# Battery_charger.net
KiCad netlist of a schematic drawn in Altium Designer
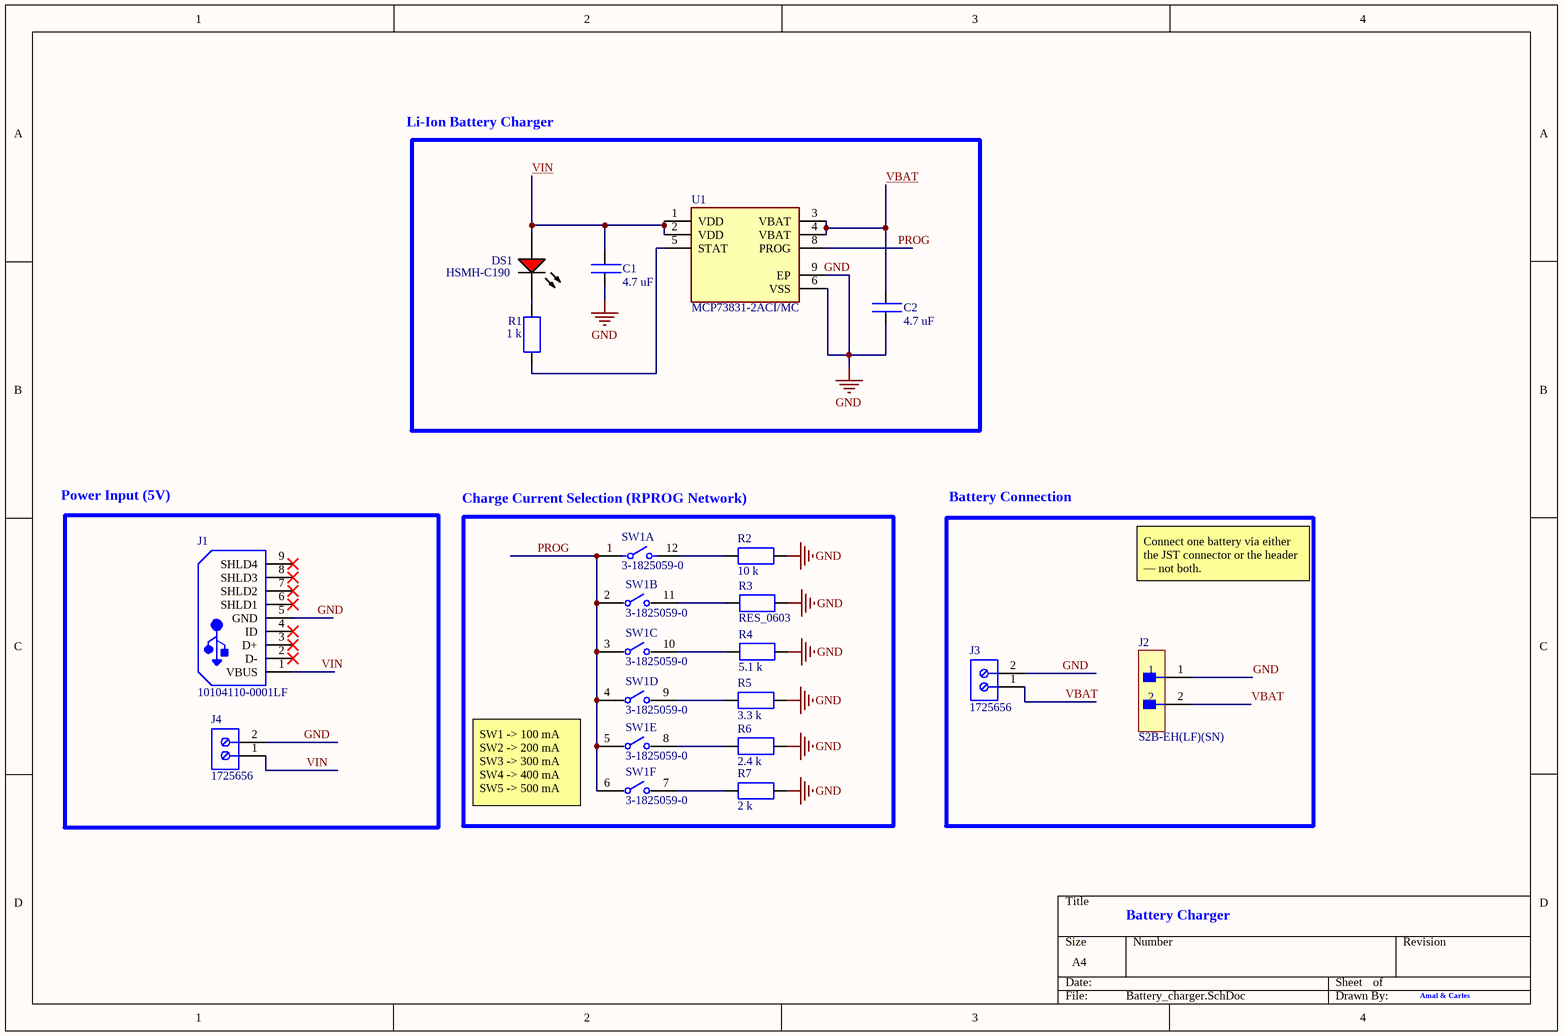
[diagram p0: Battery_charger.SchDoc]

(export (version "E")
  (design (tool "Eeschema 10.0.6"))
  (components
    (comp (ref "C1")
      (value "4.7 uF")
      (footprint "CAP_0603")
      (description "Capacitor SMD 0603 Generic")
      (fields
        (field (name "MANUFACTURER") "YAGEO")
        (field (name "MANUFACTURER PART NUMBER") "CC0603KRX7R8BB104")
      )
      (libsource (lib "Generic-Schematic-Library") (part "CAP_0603"))
    )
    (comp (ref "C2")
      (value "4.7 uF")
      (footprint "CAP_0603")
      (description "Capacitor SMD 0603 Generic")
      (fields
        (field (name "MANUFACTURER") "YAGEO")
        (field (name "MANUFACTURER PART NUMBER") "CC0603KRX7R8BB104")
      )
      (libsource (lib "Generic-Schematic-Library") (part "CAP_0603"))
    )
    (comp (ref "DS1")
      (value "HSMH-C190")
      (footprint "HSMH-C190")
      (description "LED Uni-Color Red, 65 mW, 20 mA, -40 to 85 degC, 2-Pin SMD, RoHS, Tape and Reel")
      (libsource (lib "Generic-Schematic-Library") (part "HSMH-C190"))
    )
    (comp (ref "J1")
      (value "10104110-0001LF")
      (footprint "FCI-10104110-0001LF_V")
      (description "Micro USB, Receptacle, -55 to 85 degC, 5-Pin SMD, RoHS, Tape and Reel")
      (fields (field (name "MANUFACTURER") "FCI Electronics"))
      (libsource (lib "Generic-Schematic-Library") (part "CMP-2000-05823-1"))
    )
    (comp (ref "J2")
      (value "S2B-EH(LF)(SN)")
      (footprint "FP-S2B-EH_LF_SN-MFG")
      (libsource (lib "Generic-Schematic-Library") (part "CMP-00504-00248789-1"))
    )
    (comp (ref "J3")
      (value "1725656")
      (footprint "PHOE-1725656-2")
      (description "Male Header, Pitch 2.54 mm, 1 x 2 Position, Height 9 mm, Tail Length 3.5 mm")
      (fields (field (name "MANUFACTURER") "Phoenix Contact"))
      (libsource (lib "Generic-Schematic-Library") (part "CMP-2000-05299-1"))
    )
    (comp (ref "J4")
      (value "1725656")
      (footprint "PHOE-1725656-2")
      (description "Male Header, Pitch 2.54 mm, 1 x 2 Position, Height 9 mm, Tail Length 3.5 mm")
      (fields (field (name "MANUFACTURER") "Phoenix Contact"))
      (libsource (lib "Generic-Schematic-Library") (part "CMP-2000-05299-1"))
    )
    (comp (ref "R1")
      (value "1 k")
      (footprint "RES_0603")
      (description "Resistor SMD 0603 Generic")
      (fields
        (field (name "MANUFACTURER") "YAGEO")
        (field (name "MANUFACTURER PART NUMBER") "NT0603BRD0711K1L")
      )
      (libsource (lib "Generic-Schematic-Library") (part "RES_0603"))
    )
    (comp (ref "R2")
      (value "10 k")
      (footprint "RES_0603")
      (description "Resistor SMD 0603 Generic")
      (fields
        (field (name "MANUFACTURER") "YAGEO")
        (field (name "MANUFACTURER PART NUMBER") "NT0603BRD0711K1L")
      )
      (libsource (lib "Generic-Schematic-Library") (part "RES_0603"))
    )
    (comp (ref "R3")
      (value "RES_0603")
      (footprint "RES_0603")
      (description "Resistor SMD 0603 Generic")
      (fields
        (field (name "MANUFACTURER") "YAGEO")
        (field (name "MANUFACTURER PART NUMBER") "NT0603BRD0711K1L")
      )
      (libsource (lib "Generic-Schematic-Library") (part "RES_0603"))
    )
    (comp (ref "R4")
      (value "5.1 k")
      (footprint "RES_0603")
      (description "Resistor SMD 0603 Generic")
      (fields
        (field (name "MANUFACTURER") "YAGEO")
        (field (name "MANUFACTURER PART NUMBER") "NT0603BRD0711K1L")
      )
      (libsource (lib "Generic-Schematic-Library") (part "RES_0603"))
    )
    (comp (ref "R5")
      (value "3.3 k")
      (footprint "RES_0603")
      (description "Resistor SMD 0603 Generic")
      (fields
        (field (name "MANUFACTURER") "YAGEO")
        (field (name "MANUFACTURER PART NUMBER") "NT0603BRD0711K1L")
      )
      (libsource (lib "Generic-Schematic-Library") (part "RES_0603"))
    )
    (comp (ref "R6")
      (value "2.4 k")
      (footprint "RES_0603")
      (description "Resistor SMD 0603 Generic")
      (fields
        (field (name "MANUFACTURER") "YAGEO")
        (field (name "MANUFACTURER PART NUMBER") "NT0603BRD0711K1L")
      )
      (libsource (lib "Generic-Schematic-Library") (part "RES_0603"))
    )
    (comp (ref "R7")
      (value "2 k")
      (footprint "RES_0603")
      (description "Resistor SMD 0603 Generic")
      (fields
        (field (name "MANUFACTURER") "YAGEO")
        (field (name "MANUFACTURER PART NUMBER") "NT0603BRD0711K1L")
      )
      (libsource (lib "Generic-Schematic-Library") (part "RES_0603"))
    )
    (comp (ref "SW1")
      (value "3-1825059-0")
      (footprint "FP-3-1825059-0-MFG")
      (description "SWITCH SLIDE DIP SPST 100MA 24V")
      (libsource (lib "Generic-Schematic-Library") (part "CMP-03400-000026-1"))
    )
    (comp (ref "U1")
      (value "MCP73831-2ACI/MC")
      (footprint "SON50P200X300X100-9N")
      (fields (field (name "MF") "Microchip"))
      (libsource (lib "Generic-Schematic-Library") (part "MCP73831-2ACI/MC"))
    )
  )
  (nets
    (net (code "1") (name "/PROG") (class "Default")
      (node (ref "SW1") (pin "1") (pinfunction "1_1") (pintype "passive"))
      (node (ref "SW1") (pin "2") (pinfunction "2_2") (pintype "passive"))
      (node (ref "SW1") (pin "3") (pinfunction "3_3") (pintype "passive"))
      (node (ref "SW1") (pin "4") (pinfunction "4_4") (pintype "passive"))
      (node (ref "SW1") (pin "5") (pinfunction "5_5") (pintype "passive"))
      (node (ref "SW1") (pin "6") (pinfunction "6_6") (pintype "passive"))
      (node (ref "U1") (pin "8") (pinfunction "PROG_8") (pintype "passive"))
    )
    (net (code "2") (name "/VBAT") (class "Default")
      (node (ref "C2") (pin "2") (pinfunction "2_2") (pintype "passive"))
      (node (ref "J2") (pin "2") (pinfunction "2_2") (pintype "passive"))
      (node (ref "J3") (pin "1") (pinfunction "1_1") (pintype "passive"))
      (node (ref "U1") (pin "3") (pinfunction "VBAT_3") (pintype "passive"))
      (node (ref "U1") (pin "4") (pinfunction "VBAT_4") (pintype "passive"))
    )
    (net (code "3") (name "/VIN") (class "Default")
      (node (ref "C1") (pin "2") (pinfunction "2_2") (pintype "passive"))
      (node (ref "DS1") (pin "1") (pinfunction "A_1") (pintype "passive"))
      (node (ref "J1") (pin "1") (pinfunction "VBUS_1") (pintype "power_in"))
      (node (ref "J4") (pin "1") (pinfunction "1_1") (pintype "passive"))
      (node (ref "U1") (pin "1") (pinfunction "VDD_1") (pintype "power_in"))
      (node (ref "U1") (pin "2") (pinfunction "VDD_2") (pintype "power_in"))
    )
    (net (code "4") (name "GND") (class "Default")
      (node (ref "C1") (pin "1") (pinfunction "1_1") (pintype "passive"))
      (node (ref "C2") (pin "1") (pinfunction "1_1") (pintype "passive"))
      (node (ref "J1") (pin "5") (pinfunction "GND_5") (pintype "power_in"))
      (node (ref "J2") (pin "1") (pinfunction "1_1") (pintype "passive"))
      (node (ref "J3") (pin "2") (pinfunction "2_2") (pintype "passive"))
      (node (ref "J4") (pin "2") (pinfunction "2_2") (pintype "passive"))
      (node (ref "R2") (pin "2") (pinfunction "2_2") (pintype "passive"))
      (node (ref "R3") (pin "2") (pinfunction "2_2") (pintype "passive"))
      (node (ref "R4") (pin "2") (pinfunction "2_2") (pintype "passive"))
      (node (ref "R5") (pin "2") (pinfunction "2_2") (pintype "passive"))
      (node (ref "R6") (pin "2") (pinfunction "2_2") (pintype "passive"))
      (node (ref "R7") (pin "2") (pinfunction "2_2") (pintype "passive"))
      (node (ref "U1") (pin "6") (pinfunction "VSS_6") (pintype "power_in"))
      (node (ref "U1") (pin "9") (pinfunction "EP_9") (pintype "power_in"))
    )
    (net (code "5") (name "Net-(DS1-K)") (class "Default")
      (node (ref "DS1") (pin "2") (pinfunction "K_2") (pintype "passive"))
      (node (ref "R1") (pin "2") (pinfunction "2_2") (pintype "passive"))
    )
    (net (code "6") (name "Net-(R2-Pad1)") (class "Default")
      (node (ref "R2") (pin "1") (pinfunction "1_1") (pintype "passive"))
      (node (ref "SW1") (pin "12") (pinfunction "12_12") (pintype "passive"))
    )
    (net (code "7") (name "Net-(R3-Pad1)") (class "Default")
      (node (ref "R3") (pin "1") (pinfunction "1_1") (pintype "passive"))
      (node (ref "SW1") (pin "11") (pinfunction "11_11") (pintype "passive"))
    )
    (net (code "8") (name "Net-(R4-Pad1)") (class "Default")
      (node (ref "R4") (pin "1") (pinfunction "1_1") (pintype "passive"))
      (node (ref "SW1") (pin "10") (pinfunction "10_10") (pintype "passive"))
    )
    (net (code "9") (name "Net-(R5-Pad1)") (class "Default")
      (node (ref "R5") (pin "1") (pinfunction "1_1") (pintype "passive"))
      (node (ref "SW1") (pin "9") (pinfunction "9_9") (pintype "passive"))
    )
    (net (code "10") (name "Net-(R6-Pad1)") (class "Default")
      (node (ref "R6") (pin "1") (pinfunction "1_1") (pintype "passive"))
      (node (ref "SW1") (pin "8") (pinfunction "8_8") (pintype "passive"))
    )
    (net (code "11") (name "Net-(R7-Pad1)") (class "Default")
      (node (ref "R7") (pin "1") (pinfunction "1_1") (pintype "passive"))
      (node (ref "SW1") (pin "7") (pinfunction "7_7") (pintype "passive"))
    )
    (net (code "12") (name "Net-(U1-STAT)") (class "Default")
      (node (ref "R1") (pin "1") (pinfunction "1_1") (pintype "passive"))
      (node (ref "U1") (pin "5") (pinfunction "STAT_5") (pintype "passive"))
    )
    (net (code "13") (name "unconnected-(J1-D+-Pad3)") (class "Default")
      (node (ref "J1") (pin "3") (pinfunction "D+_3") (pintype "passive+no_connect"))
    )
    (net (code "14") (name "unconnected-(J1-D--Pad2)") (class "Default")
      (node (ref "J1") (pin "2") (pinfunction "D-_2") (pintype "passive+no_connect"))
    )
    (net (code "15") (name "unconnected-(J1-ID-Pad4)") (class "Default")
      (node (ref "J1") (pin "4") (pinfunction "ID_4") (pintype "passive+no_connect"))
    )
    (net (code "16") (name "unconnected-(J1-SHLD1-Pad6)") (class "Default")
      (node (ref "J1") (pin "6") (pinfunction "SHLD1_6") (pintype "passive+no_connect"))
    )
    (net (code "17") (name "unconnected-(J1-SHLD2-Pad7)") (class "Default")
      (node (ref "J1") (pin "7") (pinfunction "SHLD2_7") (pintype "passive+no_connect"))
    )
    (net (code "18") (name "unconnected-(J1-SHLD3-Pad8)") (class "Default")
      (node (ref "J1") (pin "8") (pinfunction "SHLD3_8") (pintype "passive+no_connect"))
    )
    (net (code "19") (name "unconnected-(J1-SHLD4-Pad9)") (class "Default")
      (node (ref "J1") (pin "9") (pinfunction "SHLD4_9") (pintype "passive+no_connect"))
    )
  )
)
